# AIL_2_Schem.net
KiCad netlist of a schematic drawn in Altium Designer
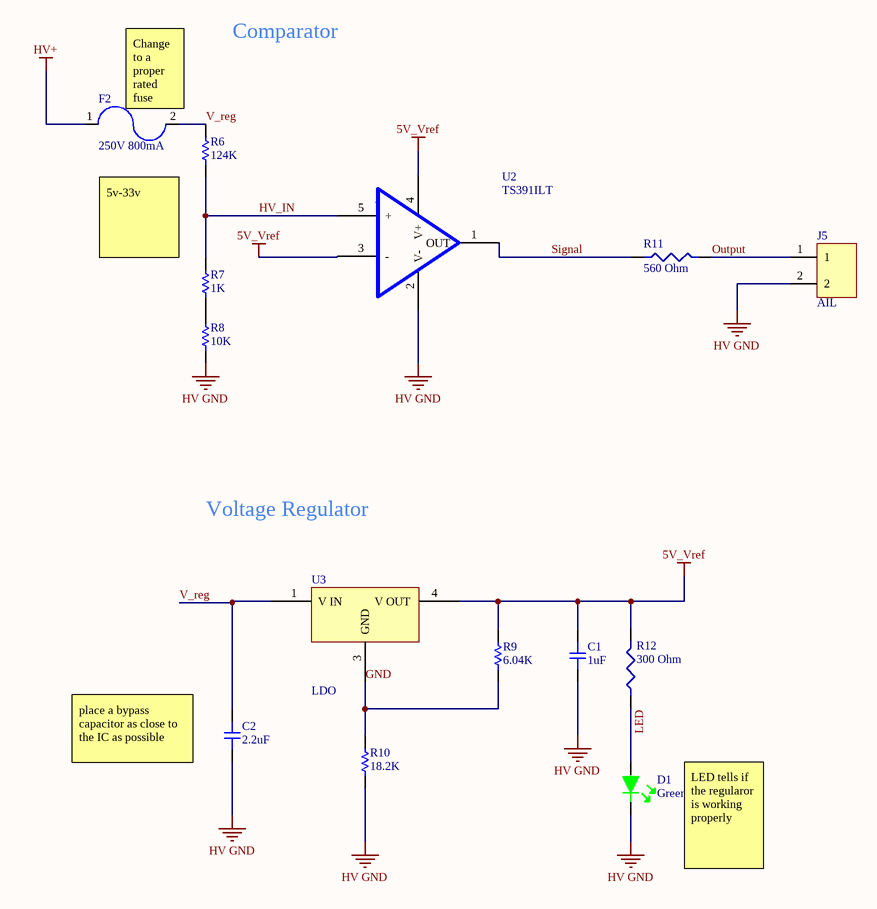
[diagram p0: AIL_2_Schem.SchDoc]

(export (version "E")
  (design (tool "Eeschema 10.0.6"))
  (components
    (comp (ref "C1")
      (value "1uF")
      (footprint "CAP-0603")
      (description "CAP CER 1UF 16V X7R 0603")
      (fields
        (field (name "MANUFACTURER") "KEMET")
        (field (name "MANUFACTURER PART NUMBER") "C0603C105K4RACTU")
      )
      (libsource (lib "Capacitors") (part "0603-1uF-16V"))
    )
    (comp (ref "C2")
      (value "2.2uF")
      (footprint "CAP-2220")
      (description "CAP CER 2.2UF 450V X6S 2220")
      (fields
        (field (name "MANUFACTURER") "TDK")
        (field (name "MANUFACTURER PART NUMBER") "C5750X6S2W225K250KA")
      )
      (libsource (lib "Capacitors") (part "2220-2.2uF-450V"))
    )
    (comp (ref "D1")
      (value "Green")
      (footprint "LED-0603")
      (description "LED GREEN CLEAR 0603 SMD")
      (fields
        (field (name "MANUFACTURER") "Wurth Electronics")
        (field (name "MANUFACTURER PART NUMBER") "150060VS75000")
      )
      (libsource (lib "LEDs") (part "LED-Green"))
    )
    (comp (ref "F2")
      (value "250V 800mA")
      (footprint "FUSE_SMD")
      (fields (field (name "MANUFACTURER") "Bel") (field (name "MANUFACTURER PART NUMBER") "0678D0800-02"))
      (libsource (lib "AIL") (part "0678D0800-02"))
    )
    (comp (ref "J5")
      (value "AIL")
      (footprint "2PIN")
      (description "CONN HEADER R/A 2POS 2.54MM")
      (fields (field (name "MANUFACTURER") "Molex") (field (name "MANUFACTURER PART NUMBER") "0705530106"))
      (libsource (lib "Connectors") (part "2PIN"))
    )
    (comp (ref "R6")
      (value "124K")
      (footprint "RES-0603")
      (description "RES 124K OHM 1% 1/10W 0603")
      (fields
        (field (name "MANUFACTURER") "Stackpole Electronics")
        (field (name "MANUFACTURER PART NUMBER") "RMCF0603FT124K")
      )
      (libsource (lib "Resistors") (part "0603-124KR"))
    )
    (comp (ref "R7")
      (value "1K")
      (footprint "RES-0603")
      (description "RES SMD 1K OHM 1% 1/10W 0603")
      (fields
        (field (name "MANUFACTURER") "Vishay Dale")
        (field (name "MANUFACTURER PART NUMBER") "CRCW06031K00FKEA")
      )
      (libsource (lib "Resistors") (part "0603-1KR"))
    )
    (comp (ref "R8")
      (value "10K")
      (footprint "RES-0603")
      (description "RES SMD 10K OHM 5% 1/10W 0603")
      (fields
        (field (name "MANUFACTURER") "Yageo")
        (field (name "MANUFACTURER PART NUMBER") "RC0603JR-0710KL")
      )
      (libsource (lib "Resistors") (part "0603-10KR"))
    )
    (comp (ref "R9")
      (value "6.04K")
      (footprint "RES-0603")
      (description "RES 6.04K OHM 1% 1/10W 0603")
      (fields
        (field (name "MANUFACTURER") "Stackpole Electronics")
        (field (name "MANUFACTURER PART NUMBER") "RMCF0603FT6K04")
      )
      (libsource (lib "Resistors") (part "0603-6.04KR"))
    )
    (comp (ref "R10")
      (value "18.2K")
      (footprint "RES-0603")
      (description "RES 18.2K OHM 1% 1/10W 0603")
      (fields
        (field (name "MANUFACTURER") "Stackpole Electronics")
        (field (name "MANUFACTURER PART NUMBER") "RMCF0603FT18K2")
      )
      (libsource (lib "Resistors") (part "0603-18.2KR"))
    )
    (comp (ref "R11")
      (value "560 Ohm")
      (footprint "RESC2012X06N")
      (description "RES SMD 560 OHM 5% 0.4W 0805")
      (fields (field (name "MANUFACTURER") "Rohm") (field (name "MANUFACTURER PART NUMBER") "ESR10EZPJ561"))
      (libsource (lib "AIL") (part "ESR10EZPJ561"))
    )
    (comp (ref "R12")
      (value "300 Ohm")
      (footprint "RESC1608X06N")
      (description "RES SMD 300 OHM 0.5% 1/16W 0603")
      (fields
        (field (name "MANUFACTURER") "Susumu")
        (field (name "MANUFACTURER PART NUMBER") "RR0816P-301-D")
      )
      (libsource (lib "AIL") (part "RR0816P-301-D"))
    )
    (comp (ref "U2")
      (value "TS391ILT")
      (footprint "SOT95P280X145-5N")
      (description "COMPARATOR, SINGLE, MICROPWR, 5SOT23")
      (fields (field (name "MANUFACTURER") "STMicroelectronics"))
      (libsource (lib "AIL") (part "TS391ILT"))
    )
    (comp (ref "U3")
      (value "LDO")
      (footprint "DPAK228P998X235-3N")
      (description "Standard Regulator Pos 1.2V to 440V 0.01A 3-Pin(2+Tab) TO-252")
      (fields (field (name "MANUFACTURER") "Microchip") (field (name "MANUFACTURER PART NUMBER") "LR8K4-G"))
      (libsource (lib "AIL") (part "LR8K4-G"))
    )
  )
  (nets
    (net (code "1") (name "/GND") (class "Default")
      (node (ref "R10") (pin "2") (pinfunction "2_2") (pintype "passive"))
      (node (ref "R9") (pin "1") (pinfunction "1_1") (pintype "passive"))
      (node (ref "U3") (pin "3") (pinfunction "GND_3") (pintype "passive"))
    )
    (net (code "2") (name "/HV_IN") (class "Default")
      (node (ref "R6") (pin "1") (pinfunction "1_1") (pintype "passive"))
      (node (ref "R7") (pin "2") (pinfunction "2_2") (pintype "passive"))
      (node (ref "U2") (pin "5") (pinfunction "+_5") (pintype "passive"))
    )
    (net (code "3") (name "/LED") (class "Default")
      (node (ref "D1") (pin "1") (pinfunction "1_1") (pintype "passive"))
      (node (ref "R12") (pin "1") (pinfunction "1_1") (pintype "passive"))
    )
    (net (code "4") (name "/Output") (class "Default")
      (node (ref "J5") (pin "1") (pinfunction "1_1") (pintype "passive"))
      (node (ref "R11") (pin "2") (pinfunction "2_2") (pintype "passive"))
    )
    (net (code "5") (name "/Signal") (class "Default")
      (node (ref "R11") (pin "1") (pinfunction "1_1") (pintype "passive"))
      (node (ref "U2") (pin "1") (pinfunction "OUT_1") (pintype "passive"))
    )
    (net (code "6") (name "/V_reg") (class "Default")
      (node (ref "C2") (pin "2") (pinfunction "2_2") (pintype "passive"))
      (node (ref "F2") (pin "2") (pinfunction "2_2") (pintype "passive"))
      (node (ref "R6") (pin "2") (pinfunction "2_2") (pintype "passive"))
      (node (ref "U3") (pin "1") (pinfunction "V_IN_1") (pintype "passive"))
    )
    (net (code "7") (name "5V_Vref") (class "Default")
      (node (ref "C1") (pin "2") (pinfunction "2_2") (pintype "passive"))
      (node (ref "R12") (pin "2") (pinfunction "2_2") (pintype "passive"))
      (node (ref "R9") (pin "2") (pinfunction "2_2") (pintype "passive"))
      (node (ref "U2") (pin "3") (pinfunction "-_3") (pintype "passive"))
      (node (ref "U2") (pin "4") (pinfunction "V+_4") (pintype "passive"))
      (node (ref "U3") (pin "4") (pinfunction "V_OUT_4") (pintype "passive"))
    )
    (net (code "8") (name "HV GND") (class "Default")
      (node (ref "C1") (pin "1") (pinfunction "1_1") (pintype "passive"))
      (node (ref "C2") (pin "1") (pinfunction "1_1") (pintype "passive"))
      (node (ref "D1") (pin "2") (pinfunction "2_2") (pintype "passive"))
      (node (ref "J5") (pin "2") (pinfunction "2_2") (pintype "passive"))
      (node (ref "R10") (pin "1") (pinfunction "1_1") (pintype "passive"))
      (node (ref "R8") (pin "1") (pinfunction "1_1") (pintype "passive"))
      (node (ref "U2") (pin "2") (pinfunction "V-_2") (pintype "passive"))
    )
    (net (code "9") (name "HV+") (class "Default")
      (node (ref "F2") (pin "1") (pinfunction "1_1") (pintype "passive"))
    )
    (net (code "10") (name "Net-(R7-Pad1)") (class "Default")
      (node (ref "R7") (pin "1") (pinfunction "1_1") (pintype "passive"))
      (node (ref "R8") (pin "2") (pinfunction "2_2") (pintype "passive"))
    )
  )
)
